# SIM_slots_1.net
KiCad netlist of a schematic drawn in Altium Designer
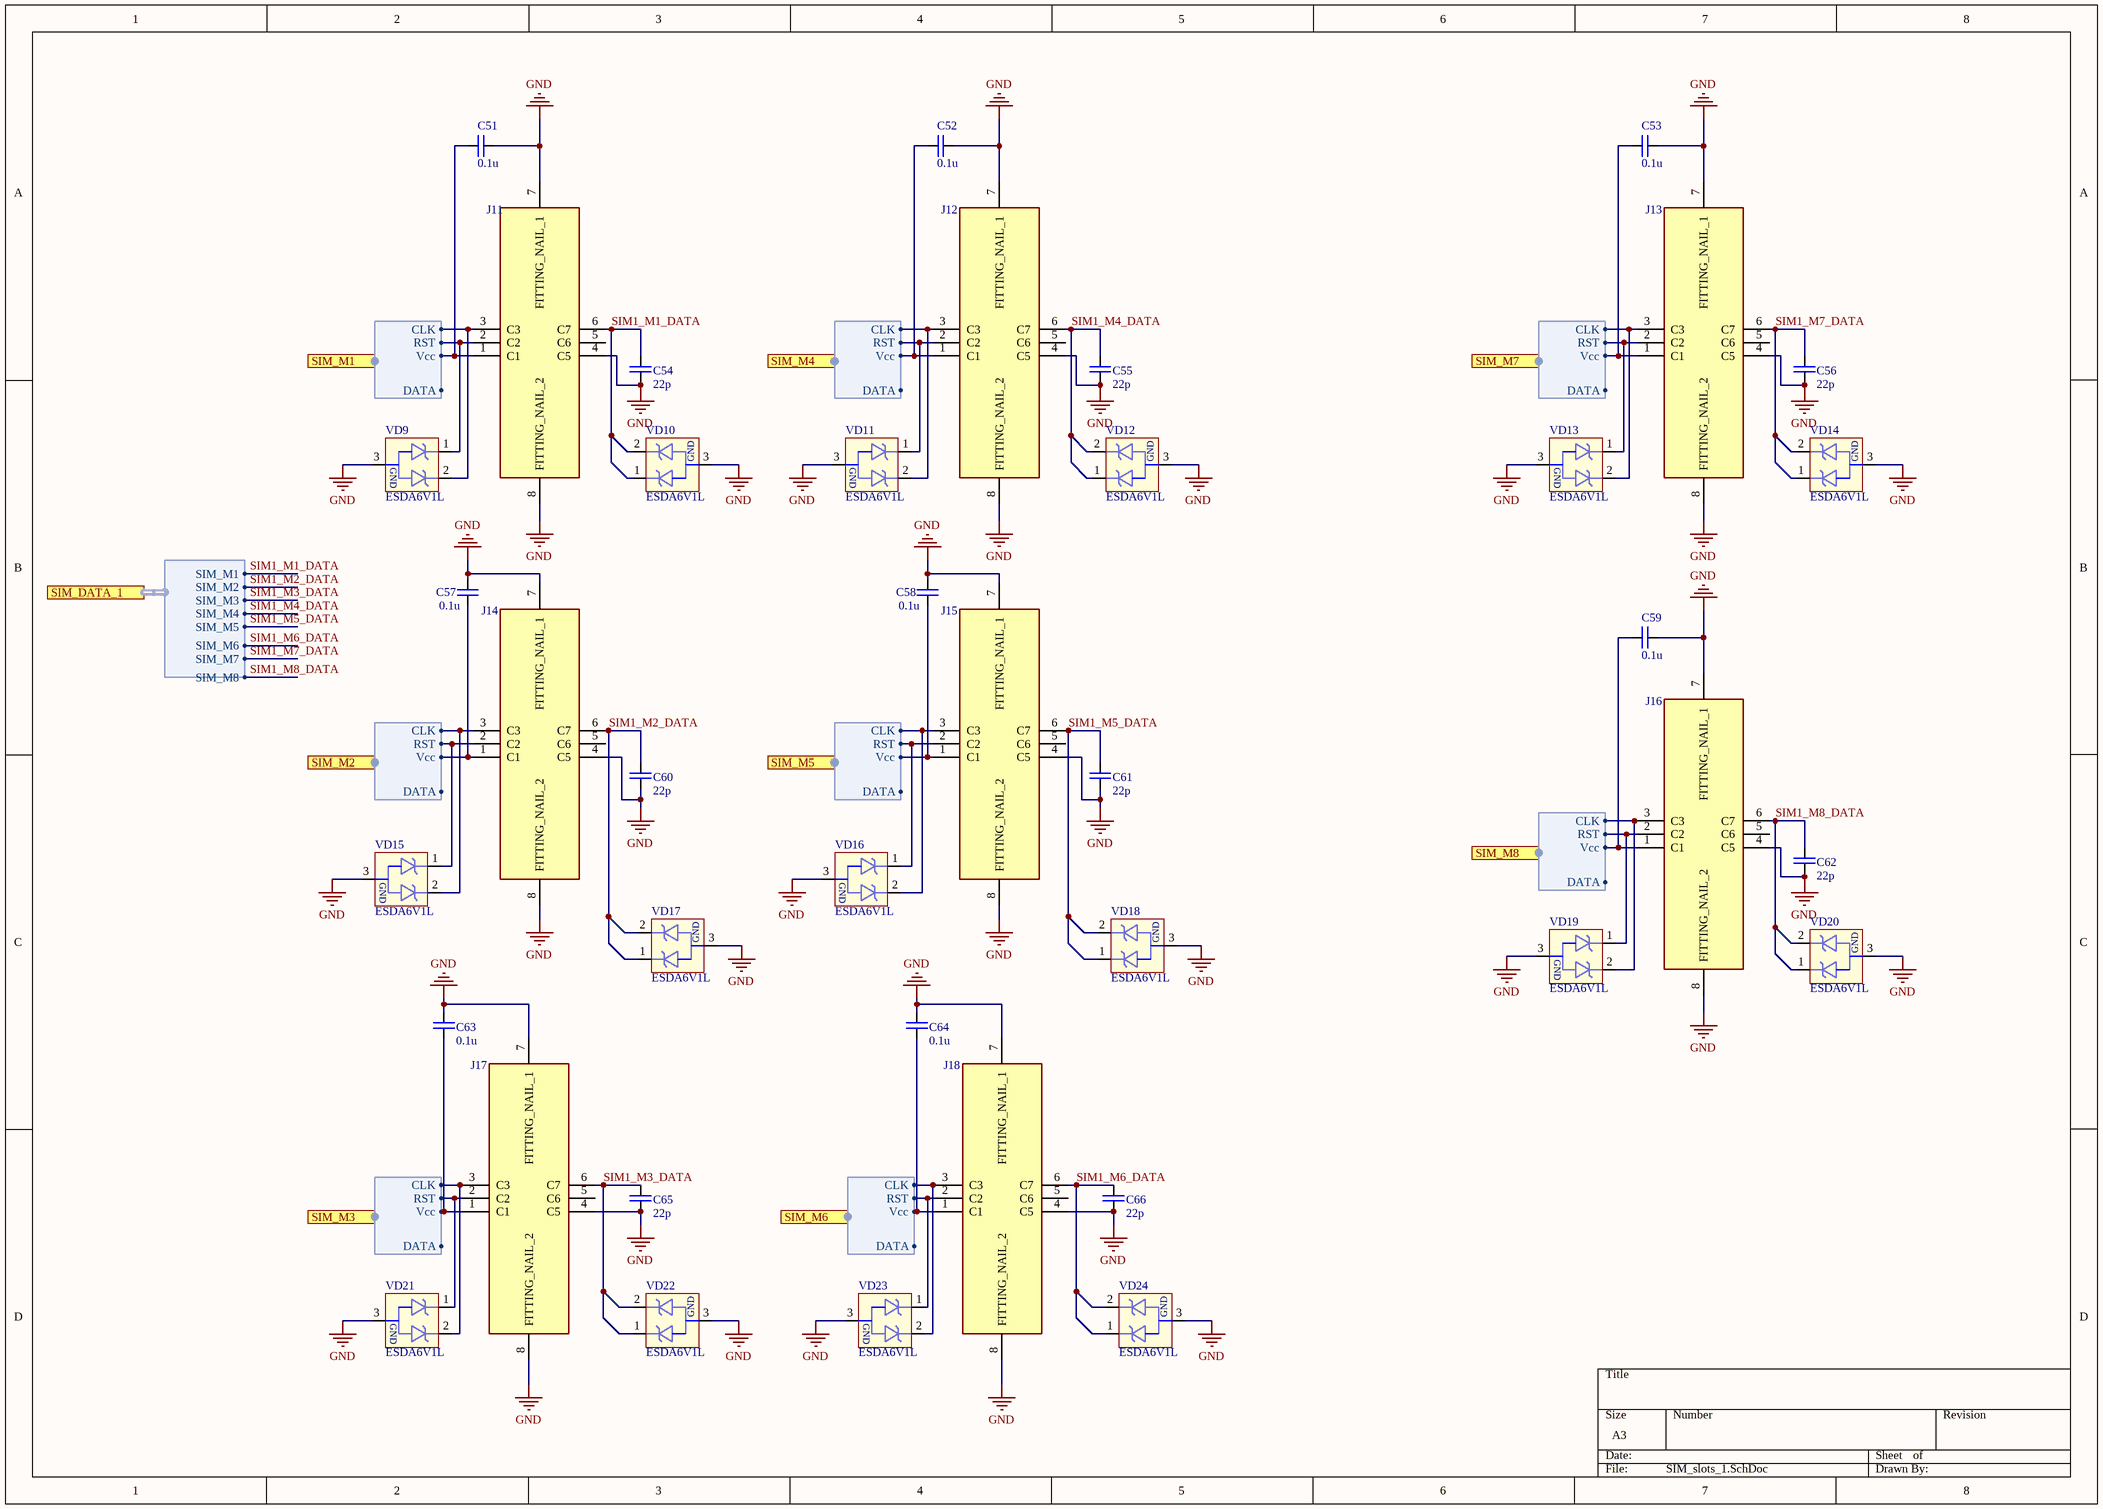
[diagram p0: SIM_slots_1.SchDoc]

(export (version "E")
  (design (tool "Eeschema 10.0.6"))
  (components
    (comp (ref "C51")
      (value "0.1u")
      (footprint "SMD_components:C0402")
      (description "Chip Capacitor 0402")
      (fields (field (name "TOLERANCE") "10%") (field (name "VOLTAGE") "25В"))
      (libsource (lib "Passives") (part "C0402"))
    )
    (comp (ref "C52")
      (value "0.1u")
      (footprint "SMD_components:C0402")
      (description "Chip Capacitor 0402")
      (fields (field (name "TOLERANCE") "10%") (field (name "VOLTAGE") "25В"))
      (libsource (lib "Passives") (part "C0402"))
    )
    (comp (ref "C53")
      (value "0.1u")
      (footprint "SMD_components:C0402")
      (description "Chip Capacitor 0402")
      (fields (field (name "TOLERANCE") "10%") (field (name "VOLTAGE") "25В"))
      (libsource (lib "Passives") (part "C0402"))
    )
    (comp (ref "C54")
      (value "22p")
      (footprint "SMD_components:C0402")
      (description "Chip Capacitor 0402")
      (fields (field (name "TOLERANCE") "10%") (field (name "VOLTAGE") "50В"))
      (libsource (lib "Passives") (part "C0402"))
    )
    (comp (ref "C55")
      (value "22p")
      (footprint "SMD_components:C0402")
      (description "Chip Capacitor 0402")
      (fields (field (name "TOLERANCE") "10%") (field (name "VOLTAGE") "50В"))
      (libsource (lib "Passives") (part "C0402"))
    )
    (comp (ref "C56")
      (value "22p")
      (footprint "SMD_components:C0402")
      (description "Chip Capacitor 0402")
      (fields (field (name "TOLERANCE") "10%") (field (name "VOLTAGE") "50В"))
      (libsource (lib "Passives") (part "C0402"))
    )
    (comp (ref "C57")
      (value "0.1u")
      (footprint "SMD_components:C0402")
      (description "Chip Capacitor 0402")
      (fields (field (name "TOLERANCE") "10%") (field (name "VOLTAGE") "25В"))
      (libsource (lib "Passives") (part "C0402"))
    )
    (comp (ref "C58")
      (value "0.1u")
      (footprint "SMD_components:C0402")
      (description "Chip Capacitor 0402")
      (fields (field (name "TOLERANCE") "10%") (field (name "VOLTAGE") "25В"))
      (libsource (lib "Passives") (part "C0402"))
    )
    (comp (ref "C59")
      (value "0.1u")
      (footprint "SMD_components:C0402")
      (description "Chip Capacitor 0402")
      (fields (field (name "TOLERANCE") "10%") (field (name "VOLTAGE") "25В"))
      (libsource (lib "Passives") (part "C0402"))
    )
    (comp (ref "C60")
      (value "22p")
      (footprint "SMD_components:C0402")
      (description "Chip Capacitor 0402")
      (fields (field (name "TOLERANCE") "10%") (field (name "VOLTAGE") "50В"))
      (libsource (lib "Passives") (part "C0402"))
    )
    (comp (ref "C61")
      (value "22p")
      (footprint "SMD_components:C0402")
      (description "Chip Capacitor 0402")
      (fields (field (name "TOLERANCE") "10%") (field (name "VOLTAGE") "50В"))
      (libsource (lib "Passives") (part "C0402"))
    )
    (comp (ref "C62")
      (value "22p")
      (footprint "SMD_components:C0402")
      (description "Chip Capacitor 0402")
      (fields (field (name "TOLERANCE") "10%") (field (name "VOLTAGE") "50В"))
      (libsource (lib "Passives") (part "C0402"))
    )
    (comp (ref "C63")
      (value "0.1u")
      (footprint "SMD_components:C0402")
      (description "Chip Capacitor 0402")
      (fields (field (name "TOLERANCE") "10%") (field (name "VOLTAGE") "25В"))
      (libsource (lib "Passives") (part "C0402"))
    )
    (comp (ref "C64")
      (value "0.1u")
      (footprint "SMD_components:C0402")
      (description "Chip Capacitor 0402")
      (fields (field (name "TOLERANCE") "10%") (field (name "VOLTAGE") "25В"))
      (libsource (lib "Passives") (part "C0402"))
    )
    (comp (ref "C65")
      (value "22p")
      (footprint "SMD_components:C0402")
      (description "Chip Capacitor 0402")
      (fields (field (name "TOLERANCE") "10%") (field (name "VOLTAGE") "50В"))
      (libsource (lib "Passives") (part "C0402"))
    )
    (comp (ref "C66")
      (value "22p")
      (footprint "SMD_components:C0402")
      (description "Chip Capacitor 0402")
      (fields (field (name "TOLERANCE") "10%") (field (name "VOLTAGE") "50В"))
      (libsource (lib "Passives") (part "C0402"))
    )
    (comp (ref "J11")
      (value "47388-2001")
      (footprint "473882001")
      (description "Connector")
      (fields (field (name "MOUSER PART NUMBER") "538-47388-2001"))
      (libsource (lib "Connectors") (part "47388-2001"))
    )
    (comp (ref "J12")
      (value "47388-2001")
      (footprint "473882001")
      (description "Connector")
      (fields (field (name "MOUSER PART NUMBER") "538-47388-2001"))
      (libsource (lib "Connectors") (part "47388-2001"))
    )
    (comp (ref "J13")
      (value "47388-2001")
      (footprint "473882001")
      (description "Connector")
      (fields (field (name "MOUSER PART NUMBER") "538-47388-2001"))
      (libsource (lib "Connectors") (part "47388-2001"))
    )
    (comp (ref "J14")
      (value "47388-2001")
      (footprint "473882001")
      (description "Connector")
      (fields (field (name "MOUSER PART NUMBER") "538-47388-2001"))
      (libsource (lib "Connectors") (part "47388-2001"))
    )
    (comp (ref "J15")
      (value "47388-2001")
      (footprint "473882001")
      (description "Connector")
      (fields (field (name "MOUSER PART NUMBER") "538-47388-2001"))
      (libsource (lib "Connectors") (part "47388-2001"))
    )
    (comp (ref "J16")
      (value "47388-2001")
      (footprint "473882001")
      (description "Connector")
      (fields (field (name "MOUSER PART NUMBER") "538-47388-2001"))
      (libsource (lib "Connectors") (part "47388-2001"))
    )
    (comp (ref "J17")
      (value "47388-2001")
      (footprint "473882001")
      (description "Connector")
      (fields (field (name "MOUSER PART NUMBER") "538-47388-2001"))
      (libsource (lib "Connectors") (part "47388-2001"))
    )
    (comp (ref "J18")
      (value "47388-2001")
      (footprint "473882001")
      (description "Connector")
      (fields (field (name "MOUSER PART NUMBER") "538-47388-2001"))
      (libsource (lib "Connectors") (part "47388-2001"))
    )
    (comp (ref "VD9")
      (value "Диод защитный, ESDA6V1L")
      (footprint "SMD_components:SOT23-3L")
      (description "Dual diode array for ESD protection")
      (fields (field (name "MANUFACTURER") "STMicroelectronics") (field (name "PARTNUMBER") "ESDA6V1L"))
      (libsource (lib "") (part "ESDA6V1L_1"))
    )
    (comp (ref "VD10")
      (value "Диод защитный, ESDA6V1L")
      (footprint "SMD_components:SOT23-3L")
      (description "Dual diode array for ESD protection")
      (fields (field (name "MANUFACTURER") "STMicroelectronics") (field (name "PARTNUMBER") "ESDA6V1L"))
      (libsource (lib "Discrete") (part "ESDA6V1L"))
    )
    (comp (ref "VD11")
      (value "Диод защитный, ESDA6V1L")
      (footprint "SMD_components:SOT23-3L")
      (description "Dual diode array for ESD protection")
      (fields (field (name "MANUFACTURER") "STMicroelectronics") (field (name "PARTNUMBER") "ESDA6V1L"))
      (libsource (lib "") (part "ESDA6V1L_1"))
    )
    (comp (ref "VD12")
      (value "Диод защитный, ESDA6V1L")
      (footprint "SMD_components:SOT23-3L")
      (description "Dual diode array for ESD protection")
      (fields (field (name "MANUFACTURER") "STMicroelectronics") (field (name "PARTNUMBER") "ESDA6V1L"))
      (libsource (lib "Discrete") (part "ESDA6V1L"))
    )
    (comp (ref "VD13")
      (value "Диод защитный, ESDA6V1L")
      (footprint "SMD_components:SOT23-3L")
      (description "Dual diode array for ESD protection")
      (fields (field (name "MANUFACTURER") "STMicroelectronics") (field (name "PARTNUMBER") "ESDA6V1L"))
      (libsource (lib "") (part "ESDA6V1L_1"))
    )
    (comp (ref "VD14")
      (value "Диод защитный, ESDA6V1L")
      (footprint "SMD_components:SOT23-3L")
      (description "Dual diode array for ESD protection")
      (fields (field (name "MANUFACTURER") "STMicroelectronics") (field (name "PARTNUMBER") "ESDA6V1L"))
      (libsource (lib "Discrete") (part "ESDA6V1L"))
    )
    (comp (ref "VD15")
      (value "Диод защитный, ESDA6V1L")
      (footprint "SMD_components:SOT23-3L")
      (description "Dual diode array for ESD protection")
      (fields (field (name "MANUFACTURER") "STMicroelectronics") (field (name "PARTNUMBER") "ESDA6V1L"))
      (libsource (lib "") (part "ESDA6V1L_1"))
    )
    (comp (ref "VD16")
      (value "Диод защитный, ESDA6V1L")
      (footprint "SMD_components:SOT23-3L")
      (description "Dual diode array for ESD protection")
      (fields (field (name "MANUFACTURER") "STMicroelectronics") (field (name "PARTNUMBER") "ESDA6V1L"))
      (libsource (lib "") (part "ESDA6V1L_1"))
    )
    (comp (ref "VD17")
      (value "Диод защитный, ESDA6V1L")
      (footprint "SMD_components:SOT23-3L")
      (description "Dual diode array for ESD protection")
      (fields (field (name "MANUFACTURER") "STMicroelectronics") (field (name "PARTNUMBER") "ESDA6V1L"))
      (libsource (lib "Discrete") (part "ESDA6V1L"))
    )
    (comp (ref "VD18")
      (value "Диод защитный, ESDA6V1L")
      (footprint "SMD_components:SOT23-3L")
      (description "Dual diode array for ESD protection")
      (fields (field (name "MANUFACTURER") "STMicroelectronics") (field (name "PARTNUMBER") "ESDA6V1L"))
      (libsource (lib "Discrete") (part "ESDA6V1L"))
    )
    (comp (ref "VD19")
      (value "Диод защитный, ESDA6V1L")
      (footprint "SMD_components:SOT23-3L")
      (description "Dual diode array for ESD protection")
      (fields (field (name "MANUFACTURER") "STMicroelectronics") (field (name "PARTNUMBER") "ESDA6V1L"))
      (libsource (lib "") (part "ESDA6V1L_1"))
    )
    (comp (ref "VD20")
      (value "Диод защитный, ESDA6V1L")
      (footprint "SMD_components:SOT23-3L")
      (description "Dual diode array for ESD protection")
      (fields (field (name "MANUFACTURER") "STMicroelectronics") (field (name "PARTNUMBER") "ESDA6V1L"))
      (libsource (lib "Discrete") (part "ESDA6V1L"))
    )
    (comp (ref "VD21")
      (value "Диод защитный, ESDA6V1L")
      (footprint "SMD_components:SOT23-3L")
      (description "Dual diode array for ESD protection")
      (fields (field (name "MANUFACTURER") "STMicroelectronics") (field (name "PARTNUMBER") "ESDA6V1L"))
      (libsource (lib "") (part "ESDA6V1L_1"))
    )
    (comp (ref "VD22")
      (value "Диод защитный, ESDA6V1L")
      (footprint "SMD_components:SOT23-3L")
      (description "Dual diode array for ESD protection")
      (fields (field (name "MANUFACTURER") "STMicroelectronics") (field (name "PARTNUMBER") "ESDA6V1L"))
      (libsource (lib "Discrete") (part "ESDA6V1L"))
    )
    (comp (ref "VD23")
      (value "Диод защитный, ESDA6V1L")
      (footprint "SMD_components:SOT23-3L")
      (description "Dual diode array for ESD protection")
      (fields (field (name "MANUFACTURER") "STMicroelectronics") (field (name "PARTNUMBER") "ESDA6V1L"))
      (libsource (lib "") (part "ESDA6V1L_1"))
    )
    (comp (ref "VD24")
      (value "Диод защитный, ESDA6V1L")
      (footprint "SMD_components:SOT23-3L")
      (description "Dual diode array for ESD protection")
      (fields (field (name "MANUFACTURER") "STMicroelectronics") (field (name "PARTNUMBER") "ESDA6V1L"))
      (libsource (lib "Discrete") (part "ESDA6V1L"))
    )
  )
  (nets
    (net (code "3") (name "/SIM1_M1_DATA") (class "Default")
      (node (ref "C54") (pin "2") (pinfunction "2_2") (pintype "passive"))
      (node (ref "J11") (pin "6") (pinfunction "C7_6") (pintype "passive"))
      (node (ref "VD10") (pin "1") (pinfunction "1_1") (pintype "passive"))
      (node (ref "VD10") (pin "2") (pinfunction "2_2") (pintype "passive"))
    )
    (net (code "4") (name "/SIM1_M2_DATA") (class "Default")
      (node (ref "C60") (pin "2") (pinfunction "2_2") (pintype "passive"))
      (node (ref "J14") (pin "6") (pinfunction "C7_6") (pintype "passive"))
      (node (ref "VD17") (pin "1") (pinfunction "1_1") (pintype "passive"))
      (node (ref "VD17") (pin "2") (pinfunction "2_2") (pintype "passive"))
    )
    (net (code "5") (name "/SIM1_M3_DATA") (class "Default")
      (node (ref "C65") (pin "2") (pinfunction "2_2") (pintype "passive"))
      (node (ref "J17") (pin "6") (pinfunction "C7_6") (pintype "passive"))
      (node (ref "VD22") (pin "1") (pinfunction "1_1") (pintype "passive"))
      (node (ref "VD22") (pin "2") (pinfunction "2_2") (pintype "passive"))
    )
    (net (code "6") (name "/SIM1_M4_DATA") (class "Default")
      (node (ref "C55") (pin "2") (pinfunction "2_2") (pintype "passive"))
      (node (ref "J12") (pin "6") (pinfunction "C7_6") (pintype "passive"))
      (node (ref "VD12") (pin "1") (pinfunction "1_1") (pintype "passive"))
      (node (ref "VD12") (pin "2") (pinfunction "2_2") (pintype "passive"))
    )
    (net (code "7") (name "/SIM1_M5_DATA") (class "Default")
      (node (ref "C61") (pin "2") (pinfunction "2_2") (pintype "passive"))
      (node (ref "J15") (pin "6") (pinfunction "C7_6") (pintype "passive"))
      (node (ref "VD18") (pin "1") (pinfunction "1_1") (pintype "passive"))
      (node (ref "VD18") (pin "2") (pinfunction "2_2") (pintype "passive"))
    )
    (net (code "8") (name "/SIM1_M6_DATA") (class "Default")
      (node (ref "C66") (pin "2") (pinfunction "2_2") (pintype "passive"))
      (node (ref "J18") (pin "6") (pinfunction "C7_6") (pintype "passive"))
      (node (ref "VD24") (pin "1") (pinfunction "1_1") (pintype "passive"))
      (node (ref "VD24") (pin "2") (pinfunction "2_2") (pintype "passive"))
    )
    (net (code "9") (name "/SIM1_M7_DATA") (class "Default")
      (node (ref "C56") (pin "2") (pinfunction "2_2") (pintype "passive"))
      (node (ref "J13") (pin "6") (pinfunction "C7_6") (pintype "passive"))
      (node (ref "VD14") (pin "1") (pinfunction "1_1") (pintype "passive"))
      (node (ref "VD14") (pin "2") (pinfunction "2_2") (pintype "passive"))
    )
    (net (code "10") (name "/SIM1_M8_DATA") (class "Default")
      (node (ref "C62") (pin "2") (pinfunction "2_2") (pintype "passive"))
      (node (ref "J16") (pin "6") (pinfunction "C7_6") (pintype "passive"))
      (node (ref "VD20") (pin "1") (pinfunction "1_1") (pintype "passive"))
      (node (ref "VD20") (pin "2") (pinfunction "2_2") (pintype "passive"))
    )
    (net (code "13") (name "GND") (class "Default")
      (node (ref "C51") (pin "2") (pinfunction "2_2") (pintype "passive"))
      (node (ref "C52") (pin "2") (pinfunction "2_2") (pintype "passive"))
      (node (ref "C53") (pin "2") (pinfunction "2_2") (pintype "passive"))
      (node (ref "C54") (pin "1") (pinfunction "1_1") (pintype "passive"))
      (node (ref "C55") (pin "1") (pinfunction "1_1") (pintype "passive"))
      (node (ref "C56") (pin "1") (pinfunction "1_1") (pintype "passive"))
      (node (ref "C57") (pin "2") (pinfunction "2_2") (pintype "passive"))
      (node (ref "C58") (pin "2") (pinfunction "2_2") (pintype "passive"))
      (node (ref "C59") (pin "2") (pinfunction "2_2") (pintype "passive"))
      (node (ref "C60") (pin "1") (pinfunction "1_1") (pintype "passive"))
      (node (ref "C61") (pin "1") (pinfunction "1_1") (pintype "passive"))
      (node (ref "C62") (pin "1") (pinfunction "1_1") (pintype "passive"))
      (node (ref "C63") (pin "2") (pinfunction "2_2") (pintype "passive"))
      (node (ref "C64") (pin "2") (pinfunction "2_2") (pintype "passive"))
      (node (ref "C65") (pin "1") (pinfunction "1_1") (pintype "passive"))
      (node (ref "C66") (pin "1") (pinfunction "1_1") (pintype "passive"))
      (node (ref "J11") (pin "4") (pinfunction "C5_4") (pintype "passive"))
      (node (ref "J11") (pin "7") (pinfunction "FITTING_NAIL_1_7") (pintype "passive"))
      (node (ref "J11") (pin "8") (pinfunction "FITTING_NAIL_2_8") (pintype "passive"))
      (node (ref "J12") (pin "4") (pinfunction "C5_4") (pintype "passive"))
      (node (ref "J12") (pin "7") (pinfunction "FITTING_NAIL_1_7") (pintype "passive"))
      (node (ref "J12") (pin "8") (pinfunction "FITTING_NAIL_2_8") (pintype "passive"))
      (node (ref "J13") (pin "4") (pinfunction "C5_4") (pintype "passive"))
      (node (ref "J13") (pin "7") (pinfunction "FITTING_NAIL_1_7") (pintype "passive"))
      (node (ref "J13") (pin "8") (pinfunction "FITTING_NAIL_2_8") (pintype "passive"))
      (node (ref "J14") (pin "4") (pinfunction "C5_4") (pintype "passive"))
      (node (ref "J14") (pin "7") (pinfunction "FITTING_NAIL_1_7") (pintype "passive"))
      (node (ref "J14") (pin "8") (pinfunction "FITTING_NAIL_2_8") (pintype "passive"))
      (node (ref "J15") (pin "4") (pinfunction "C5_4") (pintype "passive"))
      (node (ref "J15") (pin "7") (pinfunction "FITTING_NAIL_1_7") (pintype "passive"))
      (node (ref "J15") (pin "8") (pinfunction "FITTING_NAIL_2_8") (pintype "passive"))
      (node (ref "J16") (pin "4") (pinfunction "C5_4") (pintype "passive"))
      (node (ref "J16") (pin "7") (pinfunction "FITTING_NAIL_1_7") (pintype "passive"))
      (node (ref "J16") (pin "8") (pinfunction "FITTING_NAIL_2_8") (pintype "passive"))
      (node (ref "J17") (pin "4") (pinfunction "C5_4") (pintype "passive"))
      (node (ref "J17") (pin "7") (pinfunction "FITTING_NAIL_1_7") (pintype "passive"))
      (node (ref "J17") (pin "8") (pinfunction "FITTING_NAIL_2_8") (pintype "passive"))
      (node (ref "J18") (pin "4") (pinfunction "C5_4") (pintype "passive"))
      (node (ref "J18") (pin "7") (pinfunction "FITTING_NAIL_1_7") (pintype "passive"))
      (node (ref "J18") (pin "8") (pinfunction "FITTING_NAIL_2_8") (pintype "passive"))
      (node (ref "VD10") (pin "3") (pinfunction "GND_3") (pintype "passive"))
      (node (ref "VD11") (pin "3") (pinfunction "GND_3") (pintype "passive"))
      (node (ref "VD12") (pin "3") (pinfunction "GND_3") (pintype "passive"))
      (node (ref "VD13") (pin "3") (pinfunction "GND_3") (pintype "passive"))
      (node (ref "VD14") (pin "3") (pinfunction "GND_3") (pintype "passive"))
      (node (ref "VD15") (pin "3") (pinfunction "GND_3") (pintype "passive"))
      (node (ref "VD16") (pin "3") (pinfunction "GND_3") (pintype "passive"))
      (node (ref "VD17") (pin "3") (pinfunction "GND_3") (pintype "passive"))
      (node (ref "VD18") (pin "3") (pinfunction "GND_3") (pintype "passive"))
      (node (ref "VD19") (pin "3") (pinfunction "GND_3") (pintype "passive"))
      (node (ref "VD20") (pin "3") (pinfunction "GND_3") (pintype "passive"))
      (node (ref "VD21") (pin "3") (pinfunction "GND_3") (pintype "passive"))
      (node (ref "VD22") (pin "3") (pinfunction "GND_3") (pintype "passive"))
      (node (ref "VD23") (pin "3") (pinfunction "GND_3") (pintype "passive"))
      (node (ref "VD24") (pin "3") (pinfunction "GND_3") (pintype "passive"))
      (node (ref "VD9") (pin "3") (pinfunction "GND_3") (pintype "passive"))
    )
    (net (code "14") (name "Net-(J11-C1)") (class "Default")
      (node (ref "C51") (pin "1") (pinfunction "1_1") (pintype "passive"))
      (node (ref "J11") (pin "1") (pinfunction "C1_1") (pintype "passive"))
    )
    (net (code "15") (name "Net-(J11-C2)") (class "Default")
      (node (ref "J11") (pin "2") (pinfunction "C2_2") (pintype "passive"))
      (node (ref "VD9") (pin "1") (pinfunction "1_1") (pintype "passive"))
    )
    (net (code "16") (name "Net-(J11-C3)") (class "Default")
      (node (ref "J11") (pin "3") (pinfunction "C3_3") (pintype "passive"))
      (node (ref "VD9") (pin "2") (pinfunction "2_2") (pintype "passive"))
    )
    (net (code "17") (name "Net-(J12-C1)") (class "Default")
      (node (ref "C52") (pin "1") (pinfunction "1_1") (pintype "passive"))
      (node (ref "J12") (pin "1") (pinfunction "C1_1") (pintype "passive"))
    )
    (net (code "18") (name "Net-(J12-C2)") (class "Default")
      (node (ref "J12") (pin "2") (pinfunction "C2_2") (pintype "passive"))
      (node (ref "VD11") (pin "1") (pinfunction "1_1") (pintype "passive"))
    )
    (net (code "19") (name "Net-(J12-C3)") (class "Default")
      (node (ref "J12") (pin "3") (pinfunction "C3_3") (pintype "passive"))
      (node (ref "VD11") (pin "2") (pinfunction "2_2") (pintype "passive"))
    )
    (net (code "20") (name "Net-(J13-C1)") (class "Default")
      (node (ref "C53") (pin "1") (pinfunction "1_1") (pintype "passive"))
      (node (ref "J13") (pin "1") (pinfunction "C1_1") (pintype "passive"))
    )
    (net (code "21") (name "Net-(J13-C2)") (class "Default")
      (node (ref "J13") (pin "2") (pinfunction "C2_2") (pintype "passive"))
      (node (ref "VD13") (pin "1") (pinfunction "1_1") (pintype "passive"))
    )
    (net (code "22") (name "Net-(J13-C3)") (class "Default")
      (node (ref "J13") (pin "3") (pinfunction "C3_3") (pintype "passive"))
      (node (ref "VD13") (pin "2") (pinfunction "2_2") (pintype "passive"))
    )
    (net (code "23") (name "Net-(J14-C1)") (class "Default")
      (node (ref "C57") (pin "1") (pinfunction "1_1") (pintype "passive"))
      (node (ref "J14") (pin "1") (pinfunction "C1_1") (pintype "passive"))
    )
    (net (code "24") (name "Net-(J14-C2)") (class "Default")
      (node (ref "J14") (pin "2") (pinfunction "C2_2") (pintype "passive"))
      (node (ref "VD15") (pin "1") (pinfunction "1_1") (pintype "passive"))
    )
    (net (code "25") (name "Net-(J14-C3)") (class "Default")
      (node (ref "J14") (pin "3") (pinfunction "C3_3") (pintype "passive"))
      (node (ref "VD15") (pin "2") (pinfunction "2_2") (pintype "passive"))
    )
    (net (code "26") (name "Net-(J15-C1)") (class "Default")
      (node (ref "C58") (pin "1") (pinfunction "1_1") (pintype "passive"))
      (node (ref "J15") (pin "1") (pinfunction "C1_1") (pintype "passive"))
    )
    (net (code "27") (name "Net-(J15-C2)") (class "Default")
      (node (ref "J15") (pin "2") (pinfunction "C2_2") (pintype "passive"))
      (node (ref "VD16") (pin "1") (pinfunction "1_1") (pintype "passive"))
    )
    (net (code "28") (name "Net-(J15-C3)") (class "Default")
      (node (ref "J15") (pin "3") (pinfunction "C3_3") (pintype "passive"))
      (node (ref "VD16") (pin "2") (pinfunction "2_2") (pintype "passive"))
    )
    (net (code "29") (name "Net-(J16-C1)") (class "Default")
      (node (ref "C59") (pin "1") (pinfunction "1_1") (pintype "passive"))
      (node (ref "J16") (pin "1") (pinfunction "C1_1") (pintype "passive"))
    )
    (net (code "30") (name "Net-(J16-C2)") (class "Default")
      (node (ref "J16") (pin "2") (pinfunction "C2_2") (pintype "passive"))
      (node (ref "VD19") (pin "1") (pinfunction "1_1") (pintype "passive"))
    )
    (net (code "31") (name "Net-(J16-C3)") (class "Default")
      (node (ref "J16") (pin "3") (pinfunction "C3_3") (pintype "passive"))
      (node (ref "VD19") (pin "2") (pinfunction "2_2") (pintype "passive"))
    )
    (net (code "32") (name "Net-(J17-C1)") (class "Default")
      (node (ref "C63") (pin "1") (pinfunction "1_1") (pintype "passive"))
      (node (ref "J17") (pin "1") (pinfunction "C1_1") (pintype "passive"))
    )
    (net (code "33") (name "Net-(J17-C2)") (class "Default")
      (node (ref "J17") (pin "2") (pinfunction "C2_2") (pintype "passive"))
      (node (ref "VD21") (pin "1") (pinfunction "1_1") (pintype "passive"))
    )
    (net (code "34") (name "Net-(J17-C3)") (class "Default")
      (node (ref "J17") (pin "3") (pinfunction "C3_3") (pintype "passive"))
      (node (ref "VD21") (pin "2") (pinfunction "2_2") (pintype "passive"))
    )
    (net (code "35") (name "Net-(J18-C1)") (class "Default")
      (node (ref "C64") (pin "1") (pinfunction "1_1") (pintype "passive"))
      (node (ref "J18") (pin "1") (pinfunction "C1_1") (pintype "passive"))
    )
    (net (code "36") (name "Net-(J18-C2)") (class "Default")
      (node (ref "J18") (pin "2") (pinfunction "C2_2") (pintype "passive"))
      (node (ref "VD23") (pin "1") (pinfunction "1_1") (pintype "passive"))
    )
    (net (code "37") (name "Net-(J18-C3)") (class "Default")
      (node (ref "J18") (pin "3") (pinfunction "C3_3") (pintype "passive"))
      (node (ref "VD23") (pin "2") (pinfunction "2_2") (pintype "passive"))
    )
    (net (code "38") (name "unconnected-(J11-C6-Pad5)") (class "Default")
      (node (ref "J11") (pin "5") (pinfunction "C6_5") (pintype "passive"))
    )
    (net (code "39") (name "unconnected-(J12-C6-Pad5)") (class "Default")
      (node (ref "J12") (pin "5") (pinfunction "C6_5") (pintype "passive"))
    )
    (net (code "40") (name "unconnected-(J13-C6-Pad5)") (class "Default")
      (node (ref "J13") (pin "5") (pinfunction "C6_5") (pintype "passive"))
    )
    (net (code "41") (name "unconnected-(J14-C6-Pad5)") (class "Default")
      (node (ref "J14") (pin "5") (pinfunction "C6_5") (pintype "passive"))
    )
    (net (code "42") (name "unconnected-(J15-C6-Pad5)") (class "Default")
      (node (ref "J15") (pin "5") (pinfunction "C6_5") (pintype "passive"))
    )
    (net (code "43") (name "unconnected-(J16-C6-Pad5)") (class "Default")
      (node (ref "J16") (pin "5") (pinfunction "C6_5") (pintype "passive"))
    )
    (net (code "44") (name "unconnected-(J17-C6-Pad5)") (class "Default")
      (node (ref "J17") (pin "5") (pinfunction "C6_5") (pintype "passive"))
    )
    (net (code "45") (name "unconnected-(J18-C6-Pad5)") (class "Default")
      (node (ref "J18") (pin "5") (pinfunction "C6_5") (pintype "passive"))
    )
  )
)
